# Spannungsversorgung_V3.net
KiCad netlist of a schematic drawn in EAGLE
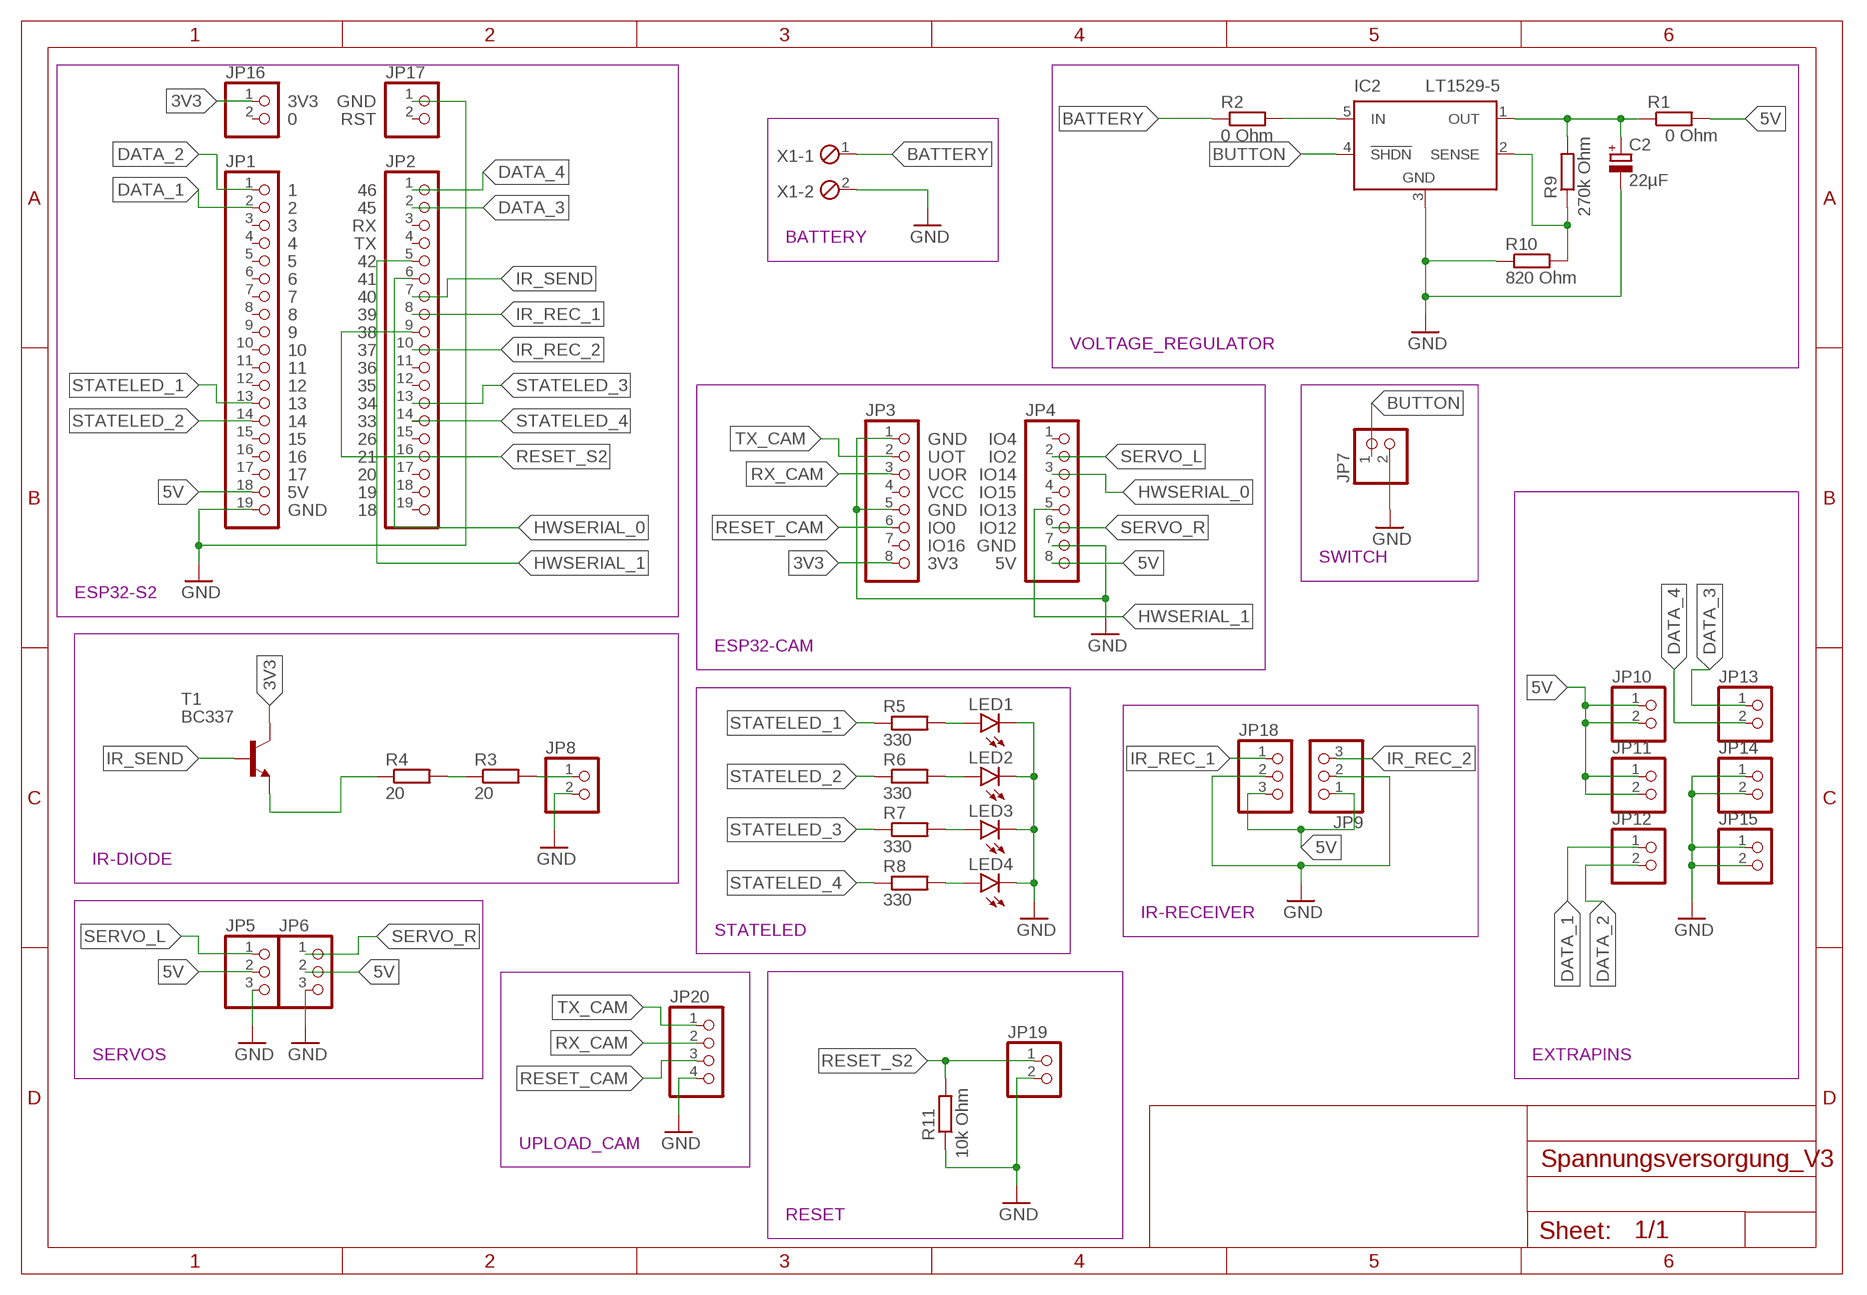
[diagram p0: schematic, sheet 1]

(export (version "E")
  (design (tool "Eeschema 10.0.6"))
  (components
    (comp (ref "C2")
      (value "22µF")
      (footprint "eagle-import:E2,5-5")
      (libsource (lib "eagle-import") (part "CPOL-EUE2.5-5"))
    )
    (comp (ref "IC2")
      (value "LT1529-5")
      (footprint "eagle-import:TO220-5")
      (libsource (lib "eagle-import") (part "LT1529T"))
    )
    (comp (ref "JP1")
      (value "PINHD-1X19")
      (footprint "eagle-import:1X19")
      (libsource (lib "eagle-import") (part "PINHD-1X19"))
    )
    (comp (ref "JP2")
      (value "PINHD-1X19")
      (footprint "eagle-import:1X19")
      (libsource (lib "eagle-import") (part "PINHD-1X19"))
    )
    (comp (ref "JP3")
      (value "PINHD-1X8")
      (footprint "eagle-import:1X08")
      (libsource (lib "eagle-import") (part "PINHD-1X8"))
    )
    (comp (ref "JP4")
      (value "PINHD-1X8")
      (footprint "eagle-import:1X08")
      (libsource (lib "eagle-import") (part "PINHD-1X8"))
    )
    (comp (ref "JP5")
      (value "PINHD-1X3")
      (footprint "eagle-import:1X03")
      (libsource (lib "eagle-import") (part "PINHD-1X3"))
    )
    (comp (ref "JP6")
      (value "PINHD-1X3")
      (footprint "eagle-import:1X03")
      (libsource (lib "eagle-import") (part "PINHD-1X3"))
    )
    (comp (ref "JP7")
      (value "PINHD-1X2")
      (footprint "eagle-import:1X02")
      (libsource (lib "eagle-import") (part "PINHD-1X2"))
    )
    (comp (ref "JP8")
      (value "PINHD-1X2")
      (footprint "eagle-import:1X02")
      (libsource (lib "eagle-import") (part "PINHD-1X2"))
    )
    (comp (ref "JP9")
      (value "PINHD-1X3")
      (footprint "eagle-import:1X03")
      (libsource (lib "eagle-import") (part "PINHD-1X3"))
    )
    (comp (ref "JP10")
      (value "PINHD-1X2")
      (footprint "eagle-import:1X02")
      (libsource (lib "eagle-import") (part "PINHD-1X2"))
    )
    (comp (ref "JP11")
      (value "PINHD-1X2")
      (footprint "eagle-import:1X02")
      (libsource (lib "eagle-import") (part "PINHD-1X2"))
    )
    (comp (ref "JP12")
      (value "PINHD-1X2")
      (footprint "eagle-import:1X02")
      (libsource (lib "eagle-import") (part "PINHD-1X2"))
    )
    (comp (ref "JP13")
      (value "PINHD-1X2")
      (footprint "eagle-import:1X02")
      (libsource (lib "eagle-import") (part "PINHD-1X2"))
    )
    (comp (ref "JP14")
      (value "PINHD-1X2")
      (footprint "eagle-import:1X02")
      (libsource (lib "eagle-import") (part "PINHD-1X2"))
    )
    (comp (ref "JP15")
      (value "PINHD-1X2")
      (footprint "eagle-import:1X02")
      (libsource (lib "eagle-import") (part "PINHD-1X2"))
    )
    (comp (ref "JP16")
      (value "PINHD-1X2")
      (footprint "eagle-import:1X02")
      (libsource (lib "eagle-import") (part "PINHD-1X2"))
    )
    (comp (ref "JP17")
      (value "PINHD-1X2")
      (footprint "eagle-import:1X02")
      (libsource (lib "eagle-import") (part "PINHD-1X2"))
    )
    (comp (ref "JP18")
      (value "PINHD-1X3")
      (footprint "eagle-import:1X03")
      (libsource (lib "eagle-import") (part "PINHD-1X3"))
    )
    (comp (ref "JP19")
      (value "PINHD-1X2")
      (footprint "eagle-import:1X02")
      (libsource (lib "eagle-import") (part "PINHD-1X2"))
    )
    (comp (ref "JP20")
      (value "PINHD-1X4")
      (footprint "eagle-import:1X04")
      (libsource (lib "eagle-import") (part "PINHD-1X4"))
    )
    (comp (ref "LED1")
      (value "LED3MM")
      (footprint "eagle-import:LED3MM")
      (libsource (lib "eagle-import") (part "LED3MM"))
    )
    (comp (ref "LED2")
      (value "LED3MM")
      (footprint "eagle-import:LED3MM")
      (libsource (lib "eagle-import") (part "LED3MM"))
    )
    (comp (ref "LED3")
      (value "LED3MM")
      (footprint "eagle-import:LED3MM")
      (libsource (lib "eagle-import") (part "LED3MM"))
    )
    (comp (ref "LED4")
      (value "LED3MM")
      (footprint "eagle-import:LED3MM")
      (libsource (lib "eagle-import") (part "LED3MM"))
    )
    (comp (ref "R1")
      (value "0 Ohm")
      (footprint "eagle-import:R0805")
      (libsource (lib "eagle-import") (part "R-EU_R0805"))
    )
    (comp (ref "R2")
      (value "0 Ohm")
      (footprint "eagle-import:R0805")
      (libsource (lib "eagle-import") (part "R-EU_R0805"))
    )
    (comp (ref "R3")
      (value "20")
      (footprint "eagle-import:0309_12")
      (libsource (lib "eagle-import") (part "R-EU_0309/12"))
    )
    (comp (ref "R4")
      (value "20")
      (footprint "eagle-import:0309_12")
      (libsource (lib "eagle-import") (part "R-EU_0309/12"))
    )
    (comp (ref "R5")
      (value "330")
      (footprint "eagle-import:R0805")
      (libsource (lib "eagle-import") (part "R-EU_R0805"))
    )
    (comp (ref "R6")
      (value "330")
      (footprint "eagle-import:R0805")
      (libsource (lib "eagle-import") (part "R-EU_R0805"))
    )
    (comp (ref "R7")
      (value "330")
      (footprint "eagle-import:R0805")
      (libsource (lib "eagle-import") (part "R-EU_R0805"))
    )
    (comp (ref "R8")
      (value "330")
      (footprint "eagle-import:R0805")
      (libsource (lib "eagle-import") (part "R-EU_R0805"))
    )
    (comp (ref "R9")
      (value "270k Ohm")
      (footprint "eagle-import:0309_12")
      (libsource (lib "eagle-import") (part "R-EU_0309/12"))
    )
    (comp (ref "R10")
      (value "820 Ohm")
      (footprint "eagle-import:0309_12")
      (libsource (lib "eagle-import") (part "R-EU_0309/12"))
    )
    (comp (ref "R11")
      (value "10k Ohm")
      (footprint "eagle-import:0309_12")
      (libsource (lib "eagle-import") (part "R-EU_0309/12"))
    )
    (comp (ref "T1")
      (value "BC337")
      (footprint "eagle-import:TO92")
      (libsource (lib "eagle-import") (part "BC337"))
    )
    (comp (ref "X1")
      (value "MPT2")
      (footprint "eagle-import:2POL254")
      (libsource (lib "eagle-import") (part "MPT2"))
    )
  )
  (nets
    (net (code "1") (name "3V3") (class "Default")
      (node (ref "JP16") (pin "1") (pinfunction "1_1") (pintype "passive"))
      (node (ref "JP3") (pin "8") (pinfunction "8_8") (pintype "passive"))
      (node (ref "T1") (pin "3") (pinfunction "C_3") (pintype "passive"))
    )
    (net (code "2") (name "5V") (class "Default")
      (node (ref "JP1") (pin "18") (pinfunction "18_18") (pintype "passive"))
      (node (ref "JP10") (pin "1") (pinfunction "1_1") (pintype "passive"))
      (node (ref "JP10") (pin "2") (pinfunction "2_2") (pintype "passive"))
      (node (ref "JP11") (pin "1") (pinfunction "1_1") (pintype "passive"))
      (node (ref "JP11") (pin "2") (pinfunction "2_2") (pintype "passive"))
      (node (ref "JP18") (pin "3") (pinfunction "3_3") (pintype "passive"))
      (node (ref "JP4") (pin "8") (pinfunction "8_8") (pintype "passive"))
      (node (ref "JP5") (pin "2") (pinfunction "2_2") (pintype "passive"))
      (node (ref "JP6") (pin "2") (pinfunction "2_2") (pintype "passive"))
      (node (ref "JP9") (pin "1") (pinfunction "1_1") (pintype "passive"))
      (node (ref "R1") (pin "2") (pinfunction "2_2") (pintype "passive"))
    )
    (net (code "3") (name "BATTERY") (class "Default")
      (node (ref "R2") (pin "1") (pinfunction "1_1") (pintype "passive"))
      (node (ref "X1") (pin "1") (pinfunction "1_1") (pintype "passive"))
    )
    (net (code "4") (name "BUTTON") (class "Default")
      (node (ref "IC2") (pin "4") (pinfunction "~{SHDN}_4") (pintype "input"))
      (node (ref "JP7") (pin "1") (pinfunction "1_1") (pintype "passive"))
    )
    (net (code "5") (name "DATA_1") (class "Default")
      (node (ref "JP1") (pin "2") (pinfunction "2_2") (pintype "passive"))
      (node (ref "JP12") (pin "1") (pinfunction "1_1") (pintype "passive"))
    )
    (net (code "6") (name "DATA_2") (class "Default")
      (node (ref "JP1") (pin "1") (pinfunction "1_1") (pintype "passive"))
      (node (ref "JP12") (pin "2") (pinfunction "2_2") (pintype "passive"))
    )
    (net (code "7") (name "DATA_3") (class "Default")
      (node (ref "JP13") (pin "1") (pinfunction "1_1") (pintype "passive"))
      (node (ref "JP2") (pin "2") (pinfunction "2_2") (pintype "passive"))
    )
    (net (code "8") (name "DATA_4") (class "Default")
      (node (ref "JP13") (pin "2") (pinfunction "2_2") (pintype "passive"))
      (node (ref "JP2") (pin "1") (pinfunction "1_1") (pintype "passive"))
    )
    (net (code "9") (name "GND") (class "Default")
      (node (ref "C2") (pin "-") (pinfunction "-_-") (pintype "passive"))
      (node (ref "IC2") (pin "3") (pinfunction "GND_3") (pintype "power_in"))
      (node (ref "JP1") (pin "19") (pinfunction "19_19") (pintype "passive"))
      (node (ref "JP14") (pin "1") (pinfunction "1_1") (pintype "passive"))
      (node (ref "JP14") (pin "2") (pinfunction "2_2") (pintype "passive"))
      (node (ref "JP15") (pin "1") (pinfunction "1_1") (pintype "passive"))
      (node (ref "JP15") (pin "2") (pinfunction "2_2") (pintype "passive"))
      (node (ref "JP17") (pin "1") (pinfunction "1_1") (pintype "passive"))
      (node (ref "JP18") (pin "2") (pinfunction "2_2") (pintype "passive"))
      (node (ref "JP19") (pin "2") (pinfunction "2_2") (pintype "passive"))
      (node (ref "JP20") (pin "4") (pinfunction "4_4") (pintype "passive"))
      (node (ref "JP3") (pin "1") (pinfunction "1_1") (pintype "passive"))
      (node (ref "JP3") (pin "5") (pinfunction "5_5") (pintype "passive"))
      (node (ref "JP4") (pin "7") (pinfunction "7_7") (pintype "passive"))
      (node (ref "JP5") (pin "3") (pinfunction "3_3") (pintype "passive"))
      (node (ref "JP6") (pin "3") (pinfunction "3_3") (pintype "passive"))
      (node (ref "JP7") (pin "2") (pinfunction "2_2") (pintype "passive"))
      (node (ref "JP8") (pin "2") (pinfunction "2_2") (pintype "passive"))
      (node (ref "JP9") (pin "2") (pinfunction "2_2") (pintype "passive"))
      (node (ref "LED1") (pin "K") (pinfunction "C_K") (pintype "passive"))
      (node (ref "LED2") (pin "K") (pinfunction "C_K") (pintype "passive"))
      (node (ref "LED3") (pin "K") (pinfunction "C_K") (pintype "passive"))
      (node (ref "LED4") (pin "K") (pinfunction "C_K") (pintype "passive"))
      (node (ref "R10") (pin "1") (pinfunction "1_1") (pintype "passive"))
      (node (ref "R11") (pin "1") (pinfunction "1_1") (pintype "passive"))
      (node (ref "X1") (pin "2") (pinfunction "1_2") (pintype "passive"))
    )
    (net (code "10") (name "HWSERIAL_0") (class "Default")
      (node (ref "JP2") (pin "6") (pinfunction "6_6") (pintype "passive"))
      (node (ref "JP4") (pin "3") (pinfunction "3_3") (pintype "passive"))
    )
    (net (code "11") (name "HWSERIAL_1") (class "Default")
      (node (ref "JP2") (pin "5") (pinfunction "5_5") (pintype "passive"))
      (node (ref "JP4") (pin "5") (pinfunction "5_5") (pintype "passive"))
    )
    (net (code "12") (name "IR_REC_1") (class "Default")
      (node (ref "JP18") (pin "1") (pinfunction "1_1") (pintype "passive"))
      (node (ref "JP2") (pin "8") (pinfunction "8_8") (pintype "passive"))
    )
    (net (code "13") (name "IR_REC_2") (class "Default")
      (node (ref "JP2") (pin "10") (pinfunction "10_10") (pintype "passive"))
      (node (ref "JP9") (pin "3") (pinfunction "3_3") (pintype "passive"))
    )
    (net (code "14") (name "IR_SEND") (class "Default")
      (node (ref "JP2") (pin "7") (pinfunction "7_7") (pintype "passive"))
      (node (ref "T1") (pin "2") (pinfunction "B_2") (pintype "passive"))
    )
    (net (code "15") (name "Net-(IC2-IN)") (class "Default")
      (node (ref "IC2") (pin "5") (pinfunction "IN_5") (pintype "input"))
      (node (ref "R2") (pin "2") (pinfunction "2_2") (pintype "passive"))
    )
    (net (code "16") (name "Net-(IC2-OUT)") (class "Default")
      (node (ref "C2") (pin "+") (pinfunction "+_+") (pintype "passive"))
      (node (ref "IC2") (pin "1") (pinfunction "OUT_1") (pintype "output"))
      (node (ref "R1") (pin "1") (pinfunction "1_1") (pintype "passive"))
      (node (ref "R9") (pin "2") (pinfunction "2_2") (pintype "passive"))
    )
    (net (code "17") (name "Net-(IC2-SENSE)") (class "Default")
      (node (ref "IC2") (pin "2") (pinfunction "SENSE_2") (pintype "input"))
      (node (ref "R10") (pin "2") (pinfunction "2_2") (pintype "passive"))
      (node (ref "R9") (pin "1") (pinfunction "1_1") (pintype "passive"))
    )
    (net (code "18") (name "Net-(JP8-Pad1)") (class "Default")
      (node (ref "JP8") (pin "1") (pinfunction "1_1") (pintype "passive"))
      (node (ref "R3") (pin "2") (pinfunction "2_2") (pintype "passive"))
    )
    (net (code "19") (name "Net-(LED1-PadA)") (class "Default")
      (node (ref "LED1") (pin "A") (pinfunction "A_A") (pintype "passive"))
      (node (ref "R5") (pin "2") (pinfunction "2_2") (pintype "passive"))
    )
    (net (code "20") (name "Net-(LED2-PadA)") (class "Default")
      (node (ref "LED2") (pin "A") (pinfunction "A_A") (pintype "passive"))
      (node (ref "R6") (pin "2") (pinfunction "2_2") (pintype "passive"))
    )
    (net (code "21") (name "Net-(LED3-PadA)") (class "Default")
      (node (ref "LED3") (pin "A") (pinfunction "A_A") (pintype "passive"))
      (node (ref "R7") (pin "2") (pinfunction "2_2") (pintype "passive"))
    )
    (net (code "22") (name "Net-(LED4-PadA)") (class "Default")
      (node (ref "LED4") (pin "A") (pinfunction "A_A") (pintype "passive"))
      (node (ref "R8") (pin "2") (pinfunction "2_2") (pintype "passive"))
    )
    (net (code "23") (name "Net-(R3-Pad1)") (class "Default")
      (node (ref "R3") (pin "1") (pinfunction "1_1") (pintype "passive"))
      (node (ref "R4") (pin "2") (pinfunction "2_2") (pintype "passive"))
    )
    (net (code "24") (name "Net-(T1-E)") (class "Default")
      (node (ref "R4") (pin "1") (pinfunction "1_1") (pintype "passive"))
      (node (ref "T1") (pin "1") (pinfunction "E_1") (pintype "passive"))
    )
    (net (code "25") (name "RESET_CAM") (class "Default")
      (node (ref "JP20") (pin "3") (pinfunction "3_3") (pintype "passive"))
      (node (ref "JP3") (pin "6") (pinfunction "6_6") (pintype "passive"))
    )
    (net (code "26") (name "RESET_S2") (class "Default")
      (node (ref "JP19") (pin "1") (pinfunction "1_1") (pintype "passive"))
      (node (ref "JP2") (pin "9") (pinfunction "9_9") (pintype "passive"))
      (node (ref "R11") (pin "2") (pinfunction "2_2") (pintype "passive"))
    )
    (net (code "27") (name "RX_CAM") (class "Default")
      (node (ref "JP20") (pin "2") (pinfunction "2_2") (pintype "passive"))
      (node (ref "JP3") (pin "3") (pinfunction "3_3") (pintype "passive"))
    )
    (net (code "28") (name "SERVO_L") (class "Default")
      (node (ref "JP4") (pin "2") (pinfunction "2_2") (pintype "passive"))
      (node (ref "JP5") (pin "1") (pinfunction "1_1") (pintype "passive"))
    )
    (net (code "29") (name "SERVO_R") (class "Default")
      (node (ref "JP4") (pin "6") (pinfunction "6_6") (pintype "passive"))
      (node (ref "JP6") (pin "1") (pinfunction "1_1") (pintype "passive"))
    )
    (net (code "30") (name "STATELED_1") (class "Default")
      (node (ref "JP1") (pin "13") (pinfunction "13_13") (pintype "passive"))
      (node (ref "R5") (pin "1") (pinfunction "1_1") (pintype "passive"))
    )
    (net (code "31") (name "STATELED_2") (class "Default")
      (node (ref "JP1") (pin "14") (pinfunction "14_14") (pintype "passive"))
      (node (ref "R6") (pin "1") (pinfunction "1_1") (pintype "passive"))
    )
    (net (code "32") (name "STATELED_3") (class "Default")
      (node (ref "JP2") (pin "13") (pinfunction "13_13") (pintype "passive"))
      (node (ref "R7") (pin "1") (pinfunction "1_1") (pintype "passive"))
    )
    (net (code "33") (name "STATELED_4") (class "Default")
      (node (ref "JP2") (pin "14") (pinfunction "14_14") (pintype "passive"))
      (node (ref "R8") (pin "1") (pinfunction "1_1") (pintype "passive"))
    )
    (net (code "34") (name "TX_CAM") (class "Default")
      (node (ref "JP20") (pin "1") (pinfunction "1_1") (pintype "passive"))
      (node (ref "JP3") (pin "2") (pinfunction "2_2") (pintype "passive"))
    )
    (net (code "35") (name "unconnected-(JP1-Pad3)") (class "Default")
      (node (ref "JP1") (pin "3") (pinfunction "3_3") (pintype "passive"))
    )
    (net (code "36") (name "unconnected-(JP1-Pad4)") (class "Default")
      (node (ref "JP1") (pin "4") (pinfunction "4_4") (pintype "passive"))
    )
    (net (code "37") (name "unconnected-(JP1-Pad5)") (class "Default")
      (node (ref "JP1") (pin "5") (pinfunction "5_5") (pintype "passive"))
    )
    (net (code "38") (name "unconnected-(JP1-Pad6)") (class "Default")
      (node (ref "JP1") (pin "6") (pinfunction "6_6") (pintype "passive"))
    )
    (net (code "39") (name "unconnected-(JP1-Pad7)") (class "Default")
      (node (ref "JP1") (pin "7") (pinfunction "7_7") (pintype "passive"))
    )
    (net (code "40") (name "unconnected-(JP1-Pad8)") (class "Default")
      (node (ref "JP1") (pin "8") (pinfunction "8_8") (pintype "passive"))
    )
    (net (code "41") (name "unconnected-(JP1-Pad9)") (class "Default")
      (node (ref "JP1") (pin "9") (pinfunction "9_9") (pintype "passive"))
    )
    (net (code "42") (name "unconnected-(JP1-Pad10)") (class "Default")
      (node (ref "JP1") (pin "10") (pinfunction "10_10") (pintype "passive"))
    )
    (net (code "43") (name "unconnected-(JP1-Pad11)") (class "Default")
      (node (ref "JP1") (pin "11") (pinfunction "11_11") (pintype "passive"))
    )
    (net (code "44") (name "unconnected-(JP1-Pad12)") (class "Default")
      (node (ref "JP1") (pin "12") (pinfunction "12_12") (pintype "passive"))
    )
    (net (code "45") (name "unconnected-(JP1-Pad15)") (class "Default")
      (node (ref "JP1") (pin "15") (pinfunction "15_15") (pintype "passive"))
    )
    (net (code "46") (name "unconnected-(JP1-Pad16)") (class "Default")
      (node (ref "JP1") (pin "16") (pinfunction "16_16") (pintype "passive"))
    )
    (net (code "47") (name "unconnected-(JP1-Pad17)") (class "Default")
      (node (ref "JP1") (pin "17") (pinfunction "17_17") (pintype "passive"))
    )
    (net (code "48") (name "unconnected-(JP2-Pad3)") (class "Default")
      (node (ref "JP2") (pin "3") (pinfunction "3_3") (pintype "passive"))
    )
    (net (code "49") (name "unconnected-(JP2-Pad4)") (class "Default")
      (node (ref "JP2") (pin "4") (pinfunction "4_4") (pintype "passive"))
    )
    (net (code "50") (name "unconnected-(JP2-Pad11)") (class "Default")
      (node (ref "JP2") (pin "11") (pinfunction "11_11") (pintype "passive"))
    )
    (net (code "51") (name "unconnected-(JP2-Pad12)") (class "Default")
      (node (ref "JP2") (pin "12") (pinfunction "12_12") (pintype "passive"))
    )
    (net (code "52") (name "unconnected-(JP2-Pad15)") (class "Default")
      (node (ref "JP2") (pin "15") (pinfunction "15_15") (pintype "passive"))
    )
    (net (code "53") (name "unconnected-(JP2-Pad16)") (class "Default")
      (node (ref "JP2") (pin "16") (pinfunction "16_16") (pintype "passive"))
    )
    (net (code "54") (name "unconnected-(JP2-Pad17)") (class "Default")
      (node (ref "JP2") (pin "17") (pinfunction "17_17") (pintype "passive"))
    )
    (net (code "55") (name "unconnected-(JP2-Pad18)") (class "Default")
      (node (ref "JP2") (pin "18") (pinfunction "18_18") (pintype "passive"))
    )
    (net (code "56") (name "unconnected-(JP2-Pad19)") (class "Default")
      (node (ref "JP2") (pin "19") (pinfunction "19_19") (pintype "passive"))
    )
    (net (code "57") (name "unconnected-(JP3-Pad4)") (class "Default")
      (node (ref "JP3") (pin "4") (pinfunction "4_4") (pintype "passive"))
    )
    (net (code "58") (name "unconnected-(JP3-Pad7)") (class "Default")
      (node (ref "JP3") (pin "7") (pinfunction "7_7") (pintype "passive"))
    )
    (net (code "59") (name "unconnected-(JP4-Pad1)") (class "Default")
      (node (ref "JP4") (pin "1") (pinfunction "1_1") (pintype "passive"))
    )
    (net (code "60") (name "unconnected-(JP4-Pad4)") (class "Default")
      (node (ref "JP4") (pin "4") (pinfunction "4_4") (pintype "passive"))
    )
    (net (code "61") (name "unconnected-(JP16-Pad2)") (class "Default")
      (node (ref "JP16") (pin "2") (pinfunction "2_2") (pintype "passive"))
    )
    (net (code "62") (name "unconnected-(JP17-Pad2)") (class "Default")
      (node (ref "JP17") (pin "2") (pinfunction "2_2") (pintype "passive"))
    )
  )
)
